# PT80.net
KiCad netlist of a schematic drawn in EAGLE
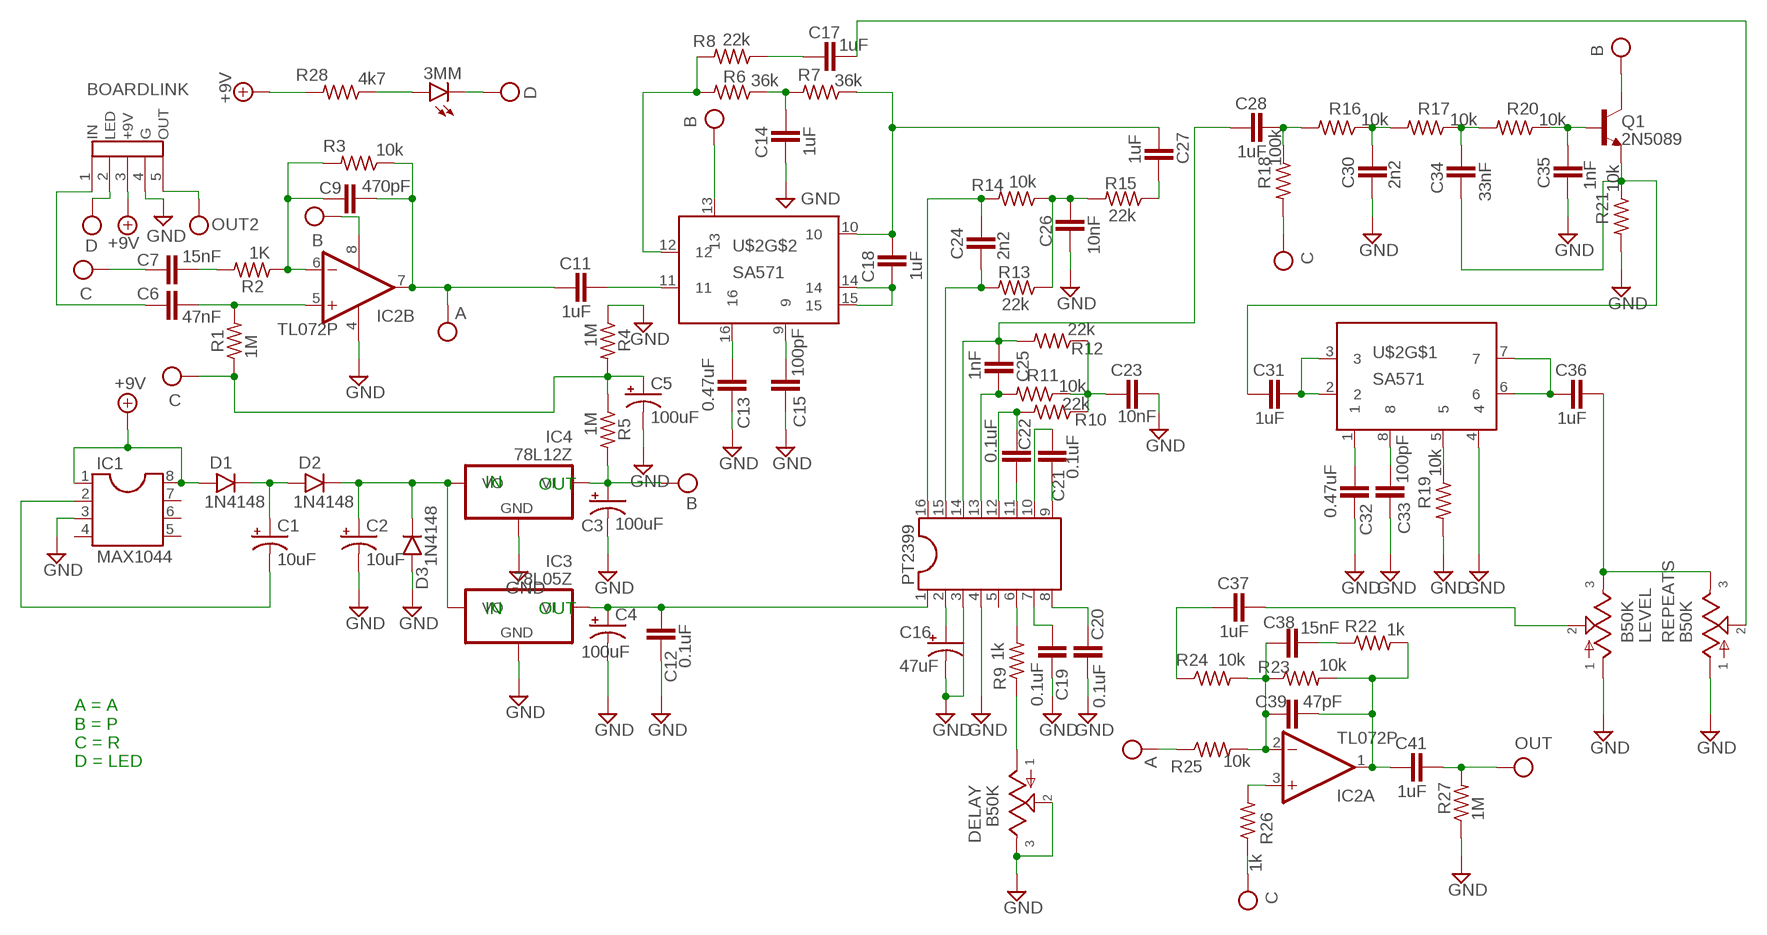
[diagram p0: schematic, sheet 1]

(export (version "E")
  (design (tool "Eeschema 10.0.6"))
  (components
    (comp (ref "3MM")
      (value "LED3MM")
      (footprint "eagle-import:LED3MM")
      (libsource (lib "eagle-import") (part "LED3MM"))
    )
    (comp (ref "C1")
      (value "10uF")
      (footprint "eagle-import:050_020_1")
      (libsource (lib "eagle-import") (part "0501"))
    )
    (comp (ref "C2")
      (value "10uF")
      (footprint "eagle-import:050_020_1")
      (libsource (lib "eagle-import") (part "0501"))
    )
    (comp (ref "C3")
      (value "100uF")
      (footprint "eagle-import:080_035_1")
      (libsource (lib "eagle-import") (part "0801"))
    )
    (comp (ref "C4")
      (value "100uF")
      (footprint "eagle-import:080_035_1")
      (libsource (lib "eagle-import") (part "0801"))
    )
    (comp (ref "C5")
      (value "100uF")
      (footprint "eagle-import:080_035_1")
      (libsource (lib "eagle-import") (part "0801"))
    )
    (comp (ref "C6")
      (value "47nF")
      (footprint "eagle-import:072X035")
      (libsource (lib "eagle-import") (part "072X0352"))
    )
    (comp (ref "C7")
      (value "15nF")
      (footprint "eagle-import:072X025")
      (libsource (lib "eagle-import") (part "072X0252"))
    )
    (comp (ref "C9")
      (value "470pF")
      (footprint "eagle-import:050X030_025")
      (libsource (lib "eagle-import") (part "050X030_0251"))
    )
    (comp (ref "C11")
      (value "1uF")
      (footprint "eagle-import:072X045")
      (libsource (lib "eagle-import") (part "072X0452"))
    )
    (comp (ref "C12")
      (value "0.1uF")
      (footprint "eagle-import:072X035")
      (libsource (lib "eagle-import") (part "072X0352"))
    )
    (comp (ref "C13")
      (value "0.47uF")
      (footprint "eagle-import:072X035")
      (libsource (lib "eagle-import") (part "072X0352"))
    )
    (comp (ref "C14")
      (value "1uF")
      (footprint "eagle-import:072X045")
      (libsource (lib "eagle-import") (part "072X0452"))
    )
    (comp (ref "C15")
      (value "100pF")
      (footprint "eagle-import:050X030_025")
      (libsource (lib "eagle-import") (part "050X030_0251"))
    )
    (comp (ref "C16")
      (value "47uF")
      (footprint "eagle-import:063_025")
      (libsource (lib "eagle-import") (part "0631"))
    )
    (comp (ref "C17")
      (value "1uF")
      (footprint "eagle-import:072X045")
      (libsource (lib "eagle-import") (part "072X0452"))
    )
    (comp (ref "C18")
      (value "1uF")
      (footprint "eagle-import:072X045")
      (libsource (lib "eagle-import") (part "072X0452"))
    )
    (comp (ref "C19")
      (value "0.1uF")
      (footprint "eagle-import:072X035")
      (libsource (lib "eagle-import") (part "072X0352"))
    )
    (comp (ref "C20")
      (value "0.1uF")
      (footprint "eagle-import:072X035")
      (libsource (lib "eagle-import") (part "072X0352"))
    )
    (comp (ref "C21")
      (value "0.1uF")
      (footprint "eagle-import:072X035")
      (libsource (lib "eagle-import") (part "072X0352"))
    )
    (comp (ref "C22")
      (value "0.1uF")
      (footprint "eagle-import:072X035")
      (libsource (lib "eagle-import") (part "072X0352"))
    )
    (comp (ref "C23")
      (value "10nF")
      (footprint "eagle-import:072X025")
      (libsource (lib "eagle-import") (part "072X0252"))
    )
    (comp (ref "C24")
      (value "2n2")
      (footprint "eagle-import:072X025")
      (libsource (lib "eagle-import") (part "072X0252"))
    )
    (comp (ref "C25")
      (value "1nF")
      (footprint "eagle-import:072X025")
      (libsource (lib "eagle-import") (part "072X0252"))
    )
    (comp (ref "C26")
      (value "10nF")
      (footprint "eagle-import:072X025")
      (libsource (lib "eagle-import") (part "072X0252"))
    )
    (comp (ref "C27")
      (value "1uF")
      (footprint "eagle-import:072X045")
      (libsource (lib "eagle-import") (part "072X0452"))
    )
    (comp (ref "C28")
      (value "1uF")
      (footprint "eagle-import:072X045")
      (libsource (lib "eagle-import") (part "072X0452"))
    )
    (comp (ref "C30")
      (value "2n2")
      (footprint "eagle-import:072X025")
      (libsource (lib "eagle-import") (part "072X0252"))
    )
    (comp (ref "C31")
      (value "1uF")
      (footprint "eagle-import:072X045")
      (libsource (lib "eagle-import") (part "072X0452"))
    )
    (comp (ref "C32")
      (value "0.47uF")
      (footprint "eagle-import:072X035")
      (libsource (lib "eagle-import") (part "072X0352"))
    )
    (comp (ref "C33")
      (value "100pF")
      (footprint "eagle-import:050X030_025")
      (libsource (lib "eagle-import") (part "050X030_0251"))
    )
    (comp (ref "C34")
      (value "33nF")
      (footprint "eagle-import:072X025")
      (libsource (lib "eagle-import") (part "072X0252"))
    )
    (comp (ref "C35")
      (value "1nF")
      (footprint "eagle-import:072X025")
      (libsource (lib "eagle-import") (part "072X0252"))
    )
    (comp (ref "C36")
      (value "1uF")
      (footprint "eagle-import:072X045")
      (libsource (lib "eagle-import") (part "072X0452"))
    )
    (comp (ref "C37")
      (value "1uF")
      (footprint "eagle-import:072X045")
      (libsource (lib "eagle-import") (part "072X0452"))
    )
    (comp (ref "C38")
      (value "15nF")
      (footprint "eagle-import:072X025")
      (libsource (lib "eagle-import") (part "072X0252"))
    )
    (comp (ref "C39")
      (value "47pF")
      (footprint "eagle-import:050X030_025")
      (libsource (lib "eagle-import") (part "050X030_0251"))
    )
    (comp (ref "C41")
      (value "1uF")
      (footprint "eagle-import:072X045")
      (libsource (lib "eagle-import") (part "072X0452"))
    )
    (comp (ref "D1")
      (value "1N4148")
      (footprint "eagle-import:DO35-3")
      (libsource (lib "eagle-import") (part "1N4148-3"))
    )
    (comp (ref "D2")
      (value "1N4148")
      (footprint "eagle-import:DO35-3")
      (libsource (lib "eagle-import") (part "1N4148-3"))
    )
    (comp (ref "D3")
      (value "1N4148")
      (footprint "eagle-import:DO35-3")
      (libsource (lib "eagle-import") (part "1N4148-3"))
    )
    (comp (ref "DELAY")
      (value "B50K")
      (footprint "eagle-import:16MM")
      (libsource (lib "eagle-import") (part "POT16MM"))
    )
    (comp (ref "IC1")
      (value "MAX1044")
      (footprint "eagle-import:DIL08")
      (libsource (lib "eagle-import") (part "MAX1044"))
    )
    (comp (ref "IC2")
      (value "TL072P")
      (footprint "eagle-import:DIL08")
      (libsource (lib "eagle-import") (part "TL072P"))
    )
    (comp (ref "IC3")
      (value "78L05Z")
      (footprint "eagle-import:TO92")
      (libsource (lib "eagle-import") (part "78ZL05"))
    )
    (comp (ref "IC4")
      (value "78L12Z")
      (footprint "eagle-import:TO92")
      (libsource (lib "eagle-import") (part "78ZL12"))
    )
    (comp (ref "LEVEL")
      (value "B50K")
      (footprint "eagle-import:16MM")
      (libsource (lib "eagle-import") (part "POT16MM"))
    )
    (comp (ref "PT2399")
      (value "DIL16")
      (footprint "eagle-import:DIL16")
      (libsource (lib "eagle-import") (part "DIL16"))
    )
    (comp (ref "Q1")
      (value "2N5089")
      (footprint "eagle-import:TO92-")
      (libsource (lib "eagle-import") (part "2N5089"))
    )
    (comp (ref "R1")
      (value "1M")
      (footprint "eagle-import:R0207_3")
      (libsource (lib "eagle-import") (part "6MM.3"))
    )
    (comp (ref "R2")
      (value "1K")
      (footprint "eagle-import:R0207_3")
      (libsource (lib "eagle-import") (part "6MM.3"))
    )
    (comp (ref "R3")
      (value "10k")
      (footprint "eagle-import:R0207_3")
      (libsource (lib "eagle-import") (part "6MM.3"))
    )
    (comp (ref "R4")
      (value "1M")
      (footprint "eagle-import:R0207_3")
      (libsource (lib "eagle-import") (part "6MM.3"))
    )
    (comp (ref "R5")
      (value "1M")
      (footprint "eagle-import:R0207_3")
      (libsource (lib "eagle-import") (part "6MM.3"))
    )
    (comp (ref "R6")
      (value "36k")
      (footprint "eagle-import:R0207_3")
      (libsource (lib "eagle-import") (part "6MM.3"))
    )
    (comp (ref "R7")
      (value "36k")
      (footprint "eagle-import:R0207_3")
      (libsource (lib "eagle-import") (part "6MM.3"))
    )
    (comp (ref "R8")
      (value "22k")
      (footprint "eagle-import:R0207_3")
      (libsource (lib "eagle-import") (part "6MM.3"))
    )
    (comp (ref "R9")
      (value "1k")
      (footprint "eagle-import:R0207_3")
      (libsource (lib "eagle-import") (part "6MM.3"))
    )
    (comp (ref "R10")
      (value "22k")
      (footprint "eagle-import:R0207_3")
      (libsource (lib "eagle-import") (part "6MM.3"))
    )
    (comp (ref "R11")
      (value "10k")
      (footprint "eagle-import:R0207_3")
      (libsource (lib "eagle-import") (part "6MM.3"))
    )
    (comp (ref "R12")
      (value "22k")
      (footprint "eagle-import:R0207_3")
      (libsource (lib "eagle-import") (part "6MM.3"))
    )
    (comp (ref "R13")
      (value "22k")
      (footprint "eagle-import:R0207_3")
      (libsource (lib "eagle-import") (part "6MM.3"))
    )
    (comp (ref "R14")
      (value "10k")
      (footprint "eagle-import:R0207_3")
      (libsource (lib "eagle-import") (part "6MM.3"))
    )
    (comp (ref "R15")
      (value "22k")
      (footprint "eagle-import:R0207_3")
      (libsource (lib "eagle-import") (part "6MM.3"))
    )
    (comp (ref "R16")
      (value "10k")
      (footprint "eagle-import:R0207_3")
      (libsource (lib "eagle-import") (part "6MM.3"))
    )
    (comp (ref "R17")
      (value "10k")
      (footprint "eagle-import:R0207_3")
      (libsource (lib "eagle-import") (part "6MM.3"))
    )
    (comp (ref "R18")
      (value "100k")
      (footprint "eagle-import:R0207_3")
      (libsource (lib "eagle-import") (part "6MM.3"))
    )
    (comp (ref "R19")
      (value "10k")
      (footprint "eagle-import:R0207_3")
      (libsource (lib "eagle-import") (part "6MM.3"))
    )
    (comp (ref "R20")
      (value "10k")
      (footprint "eagle-import:R0207_3")
      (libsource (lib "eagle-import") (part "6MM.3"))
    )
    (comp (ref "R21")
      (value "10k")
      (footprint "eagle-import:R0207_3")
      (libsource (lib "eagle-import") (part "6MM.3"))
    )
    (comp (ref "R22")
      (value "1k")
      (footprint "eagle-import:R0207_3")
      (libsource (lib "eagle-import") (part "6MM.3"))
    )
    (comp (ref "R23")
      (value "10k")
      (footprint "eagle-import:R0207_3")
      (libsource (lib "eagle-import") (part "6MM.3"))
    )
    (comp (ref "R24")
      (value "10k")
      (footprint "eagle-import:R0207_3")
      (libsource (lib "eagle-import") (part "6MM.3"))
    )
    (comp (ref "R25")
      (value "10k")
      (footprint "eagle-import:R0207_3")
      (libsource (lib "eagle-import") (part "6MM.3"))
    )
    (comp (ref "R26")
      (value "1k")
      (footprint "eagle-import:R0207_3")
      (libsource (lib "eagle-import") (part "6MM.3"))
    )
    (comp (ref "R27")
      (value "1M")
      (footprint "eagle-import:R0207_3")
      (libsource (lib "eagle-import") (part "6MM.3"))
    )
    (comp (ref "R28")
      (value "4k7")
      (footprint "eagle-import:R0207_3")
      (libsource (lib "eagle-import") (part "6MM.3"))
    )
    (comp (ref "REPEATS")
      (value "B50K")
      (footprint "eagle-import:16MM")
      (libsource (lib "eagle-import") (part "POT16MM"))
    )
    (comp (ref "U$1")
      (value "BOARDLINK")
      (footprint "eagle-import:BOARDLINK")
      (libsource (lib "eagle-import") (part "BOARDLINK"))
    )
    (comp (ref "U$2")
      (value "SA571")
      (footprint "eagle-import:DIL16")
      (libsource (lib "eagle-import") (part "SA571"))
    )
  )
  (nets
    (net (code "1") (name "+9V") (class "Default")
      (node (ref "D1") (pin "A") (pinfunction "A_A") (pintype "passive"))
      (node (ref "IC1") (pin "1") (pinfunction "1_1") (pintype "passive"))
      (node (ref "IC1") (pin "8") (pinfunction "8_8") (pintype "passive"))
      (node (ref "R28") (pin "2") (pinfunction "2_2") (pintype "passive"))
      (node (ref "U$1") (pin "3") (pinfunction "+9V_3") (pintype "bidirectional"))
    )
    (net (code "2") (name "A") (class "Default")
      (node (ref "C11") (pin "1") (pinfunction "1_1") (pintype "passive"))
      (node (ref "C9") (pin "2") (pinfunction "2_2") (pintype "passive"))
      (node (ref "IC2") (pin "7") (pinfunction "OUT_7") (pintype "output"))
      (node (ref "R25") (pin "1") (pinfunction "1_1") (pintype "passive"))
      (node (ref "R3") (pin "1") (pinfunction "1_1") (pintype "passive"))
    )
    (net (code "3") (name "B") (class "Default")
      (node (ref "C3") (pin "+") (pinfunction "+_+") (pintype "passive"))
      (node (ref "IC2") (pin "8") (pinfunction "V+_8") (pintype "power_in"))
      (node (ref "IC4") (pin "1") (pinfunction "VI_1") (pintype "input"))
      (node (ref "Q1") (pin "1") (pinfunction "C_1") (pintype "passive"))
      (node (ref "R5") (pin "2") (pinfunction "2_2") (pintype "passive"))
      (node (ref "U$2") (pin "13") (pinfunction "13_13") (pintype "bidirectional"))
    )
    (net (code "4") (name "C") (class "Default")
      (node (ref "C5") (pin "+") (pinfunction "+_+") (pintype "passive"))
      (node (ref "C7") (pin "1") (pinfunction "1_1") (pintype "passive"))
      (node (ref "R1") (pin "1") (pinfunction "1_1") (pintype "passive"))
      (node (ref "R18") (pin "2") (pinfunction "2_2") (pintype "passive"))
      (node (ref "R26") (pin "1") (pinfunction "1_1") (pintype "passive"))
      (node (ref "R4") (pin "2") (pinfunction "2_2") (pintype "passive"))
      (node (ref "R5") (pin "1") (pinfunction "1_1") (pintype "passive"))
    )
    (net (code "5") (name "D") (class "Default")
      (node (ref "3MM") (pin "K") (pinfunction "C_K") (pintype "passive"))
      (node (ref "U$1") (pin "2") (pinfunction "LED_2") (pintype "bidirectional"))
    )
    (net (code "6") (name "GND") (class "Default")
      (node (ref "C12") (pin "1") (pinfunction "1_1") (pintype "passive"))
      (node (ref "C13") (pin "2") (pinfunction "2_2") (pintype "passive"))
      (node (ref "C14") (pin "1") (pinfunction "1_1") (pintype "passive"))
      (node (ref "C15") (pin "1") (pinfunction "1_1") (pintype "passive"))
      (node (ref "C16") (pin "-") (pinfunction "-_-") (pintype "passive"))
      (node (ref "C19") (pin "2") (pinfunction "2_2") (pintype "passive"))
      (node (ref "C2") (pin "-") (pinfunction "-_-") (pintype "passive"))
      (node (ref "C20") (pin "2") (pinfunction "2_2") (pintype "passive"))
      (node (ref "C23") (pin "2") (pinfunction "2_2") (pintype "passive"))
      (node (ref "C26") (pin "1") (pinfunction "1_1") (pintype "passive"))
      (node (ref "C3") (pin "-") (pinfunction "-_-") (pintype "passive"))
      (node (ref "C30") (pin "1") (pinfunction "1_1") (pintype "passive"))
      (node (ref "C32") (pin "2") (pinfunction "2_2") (pintype "passive"))
      (node (ref "C33") (pin "1") (pinfunction "1_1") (pintype "passive"))
      (node (ref "C35") (pin "1") (pinfunction "1_1") (pintype "passive"))
      (node (ref "C4") (pin "-") (pinfunction "-_-") (pintype "passive"))
      (node (ref "C5") (pin "-") (pinfunction "-_-") (pintype "passive"))
      (node (ref "D3") (pin "A") (pinfunction "A_A") (pintype "passive"))
      (node (ref "DELAY") (pin "2") (pinfunction "2_2") (pintype "passive"))
      (node (ref "DELAY") (pin "3") (pinfunction "3_3") (pintype "passive"))
      (node (ref "IC1") (pin "3") (pinfunction "3_3") (pintype "passive"))
      (node (ref "IC2") (pin "4") (pinfunction "V-_4") (pintype "power_in"))
      (node (ref "IC3") (pin "2") (pinfunction "GND_2") (pintype "passive"))
      (node (ref "IC4") (pin "2") (pinfunction "GND_2") (pintype "passive"))
      (node (ref "LEVEL") (pin "1") (pinfunction "1_1") (pintype "passive"))
      (node (ref "PT2399") (pin "3") (pinfunction "3_3") (pintype "passive"))
      (node (ref "PT2399") (pin "4") (pinfunction "4_4") (pintype "passive"))
      (node (ref "R19") (pin "2") (pinfunction "2_2") (pintype "passive"))
      (node (ref "R21") (pin "2") (pinfunction "2_2") (pintype "passive"))
      (node (ref "R27") (pin "1") (pinfunction "1_1") (pintype "passive"))
      (node (ref "R4") (pin "1") (pinfunction "1_1") (pintype "passive"))
      (node (ref "REPEATS") (pin "1") (pinfunction "1_1") (pintype "passive"))
      (node (ref "U$1") (pin "4") (pinfunction "G_4") (pintype "bidirectional"))
      (node (ref "U$2") (pin "4") (pinfunction "4_4") (pintype "bidirectional"))
    )
    (net (code "7") (name "Net-(3MM-PadA)") (class "Default")
      (node (ref "3MM") (pin "A") (pinfunction "A_A") (pintype "passive"))
      (node (ref "R28") (pin "1") (pinfunction "1_1") (pintype "passive"))
    )
    (net (code "8") (name "Net-(C1-Pad+)") (class "Default")
      (node (ref "C1") (pin "+") (pinfunction "+_+") (pintype "passive"))
      (node (ref "D1") (pin "C") (pinfunction "C_C") (pintype "passive"))
      (node (ref "D2") (pin "A") (pinfunction "A_A") (pintype "passive"))
    )
    (net (code "9") (name "Net-(C1-Pad-)") (class "Default")
      (node (ref "C1") (pin "-") (pinfunction "-_-") (pintype "passive"))
      (node (ref "IC1") (pin "2") (pinfunction "2_2") (pintype "passive"))
    )
    (net (code "10") (name "Net-(C7-Pad2)") (class "Default")
      (node (ref "C7") (pin "2") (pinfunction "2_2") (pintype "passive"))
      (node (ref "R2") (pin "2") (pinfunction "2_2") (pintype "passive"))
    )
    (net (code "11") (name "Net-(C11-Pad2)") (class "Default")
      (node (ref "C11") (pin "2") (pinfunction "2_2") (pintype "passive"))
      (node (ref "U$2") (pin "11") (pinfunction "11_11") (pintype "bidirectional"))
    )
    (net (code "12") (name "Net-(C13-Pad1)") (class "Default")
      (node (ref "C13") (pin "1") (pinfunction "1_1") (pintype "passive"))
      (node (ref "U$2") (pin "16") (pinfunction "16_16") (pintype "bidirectional"))
    )
    (net (code "13") (name "Net-(C14-Pad2)") (class "Default")
      (node (ref "C14") (pin "2") (pinfunction "2_2") (pintype "passive"))
      (node (ref "R6") (pin "1") (pinfunction "1_1") (pintype "passive"))
      (node (ref "R7") (pin "2") (pinfunction "2_2") (pintype "passive"))
    )
    (net (code "14") (name "Net-(C15-Pad2)") (class "Default")
      (node (ref "C15") (pin "2") (pinfunction "2_2") (pintype "passive"))
      (node (ref "U$2") (pin "9") (pinfunction "9_9") (pintype "bidirectional"))
    )
    (net (code "15") (name "Net-(C16-Pad+)") (class "Default")
      (node (ref "C16") (pin "+") (pinfunction "+_+") (pintype "passive"))
      (node (ref "PT2399") (pin "2") (pinfunction "2_2") (pintype "passive"))
    )
    (net (code "16") (name "Net-(C17-Pad1)") (class "Default")
      (node (ref "C17") (pin "1") (pinfunction "1_1") (pintype "passive"))
      (node (ref "R8") (pin "1") (pinfunction "1_1") (pintype "passive"))
    )
    (net (code "17") (name "Net-(C17-Pad2)") (class "Default")
      (node (ref "C17") (pin "2") (pinfunction "2_2") (pintype "passive"))
      (node (ref "REPEATS") (pin "2") (pinfunction "2_2") (pintype "passive"))
    )
    (net (code "18") (name "Net-(C18-Pad1)") (class "Default")
      (node (ref "C18") (pin "1") (pinfunction "1_1") (pintype "passive"))
      (node (ref "U$2") (pin "14") (pinfunction "14_14") (pintype "bidirectional"))
      (node (ref "U$2") (pin "15") (pinfunction "15_15") (pintype "bidirectional"))
    )
    (net (code "19") (name "Net-(C18-Pad2)") (class "Default")
      (node (ref "C18") (pin "2") (pinfunction "2_2") (pintype "passive"))
      (node (ref "C27") (pin "1") (pinfunction "1_1") (pintype "passive"))
      (node (ref "R7") (pin "1") (pinfunction "1_1") (pintype "passive"))
      (node (ref "U$2") (pin "10") (pinfunction "10_10") (pintype "bidirectional"))
    )
    (net (code "20") (name "Net-(C19-Pad1)") (class "Default")
      (node (ref "C19") (pin "1") (pinfunction "1_1") (pintype "passive"))
      (node (ref "PT2399") (pin "7") (pinfunction "7_7") (pintype "passive"))
    )
    (net (code "21") (name "Net-(C20-Pad1)") (class "Default")
      (node (ref "C20") (pin "1") (pinfunction "1_1") (pintype "passive"))
      (node (ref "PT2399") (pin "8") (pinfunction "8_8") (pintype "passive"))
    )
    (net (code "22") (name "Net-(C21-Pad1)") (class "Default")
      (node (ref "C21") (pin "1") (pinfunction "1_1") (pintype "passive"))
      (node (ref "PT2399") (pin "10") (pinfunction "10_10") (pintype "passive"))
    )
    (net (code "23") (name "Net-(C21-Pad2)") (class "Default")
      (node (ref "C21") (pin "2") (pinfunction "2_2") (pintype "passive"))
      (node (ref "PT2399") (pin "9") (pinfunction "9_9") (pintype "passive"))
    )
    (net (code "24") (name "Net-(C22-Pad1)") (class "Default")
      (node (ref "C22") (pin "1") (pinfunction "1_1") (pintype "passive"))
      (node (ref "PT2399") (pin "12") (pinfunction "12_12") (pintype "passive"))
      (node (ref "R10") (pin "2") (pinfunction "2_2") (pintype "passive"))
    )
    (net (code "25") (name "Net-(C22-Pad2)") (class "Default")
      (node (ref "C22") (pin "2") (pinfunction "2_2") (pintype "passive"))
      (node (ref "PT2399") (pin "11") (pinfunction "11_11") (pintype "passive"))
    )
    (net (code "26") (name "Net-(C23-Pad1)") (class "Default")
      (node (ref "C23") (pin "1") (pinfunction "1_1") (pintype "passive"))
      (node (ref "R10") (pin "1") (pinfunction "1_1") (pintype "passive"))
      (node (ref "R11") (pin "1") (pinfunction "1_1") (pintype "passive"))
      (node (ref "R12") (pin "1") (pinfunction "1_1") (pintype "passive"))
    )
    (net (code "27") (name "Net-(C24-Pad1)") (class "Default")
      (node (ref "C24") (pin "1") (pinfunction "1_1") (pintype "passive"))
      (node (ref "PT2399") (pin "15") (pinfunction "15_15") (pintype "passive"))
      (node (ref "R13") (pin "2") (pinfunction "2_2") (pintype "passive"))
    )
    (net (code "28") (name "Net-(C24-Pad2)") (class "Default")
      (node (ref "C24") (pin "2") (pinfunction "2_2") (pintype "passive"))
      (node (ref "PT2399") (pin "16") (pinfunction "16_16") (pintype "passive"))
      (node (ref "R14") (pin "2") (pinfunction "2_2") (pintype "passive"))
    )
    (net (code "29") (name "Net-(C25-Pad1)") (class "Default")
      (node (ref "C25") (pin "1") (pinfunction "1_1") (pintype "passive"))
      (node (ref "PT2399") (pin "13") (pinfunction "13_13") (pintype "passive"))
      (node (ref "R11") (pin "2") (pinfunction "2_2") (pintype "passive"))
    )
    (net (code "30") (name "Net-(C25-Pad2)") (class "Default")
      (node (ref "C25") (pin "2") (pinfunction "2_2") (pintype "passive"))
      (node (ref "C28") (pin "1") (pinfunction "1_1") (pintype "passive"))
      (node (ref "PT2399") (pin "14") (pinfunction "14_14") (pintype "passive"))
      (node (ref "R12") (pin "2") (pinfunction "2_2") (pintype "passive"))
    )
    (net (code "31") (name "Net-(C26-Pad2)") (class "Default")
      (node (ref "C26") (pin "2") (pinfunction "2_2") (pintype "passive"))
      (node (ref "R13") (pin "1") (pinfunction "1_1") (pintype "passive"))
      (node (ref "R14") (pin "1") (pinfunction "1_1") (pintype "passive"))
      (node (ref "R15") (pin "2") (pinfunction "2_2") (pintype "passive"))
    )
    (net (code "32") (name "Net-(C27-Pad2)") (class "Default")
      (node (ref "C27") (pin "2") (pinfunction "2_2") (pintype "passive"))
      (node (ref "R15") (pin "1") (pinfunction "1_1") (pintype "passive"))
    )
    (net (code "33") (name "Net-(C28-Pad2)") (class "Default")
      (node (ref "C28") (pin "2") (pinfunction "2_2") (pintype "passive"))
      (node (ref "R16") (pin "2") (pinfunction "2_2") (pintype "passive"))
      (node (ref "R18") (pin "1") (pinfunction "1_1") (pintype "passive"))
    )
    (net (code "34") (name "Net-(C30-Pad2)") (class "Default")
      (node (ref "C30") (pin "2") (pinfunction "2_2") (pintype "passive"))
      (node (ref "R16") (pin "1") (pinfunction "1_1") (pintype "passive"))
      (node (ref "R17") (pin "2") (pinfunction "2_2") (pintype "passive"))
    )
    (net (code "35") (name "Net-(C31-Pad2)") (class "Default")
      (node (ref "C31") (pin "2") (pinfunction "2_2") (pintype "passive"))
      (node (ref "U$2") (pin "2") (pinfunction "2_2") (pintype "bidirectional"))
      (node (ref "U$2") (pin "3") (pinfunction "3_3") (pintype "bidirectional"))
    )
    (net (code "36") (name "Net-(C32-Pad1)") (class "Default")
      (node (ref "C32") (pin "1") (pinfunction "1_1") (pintype "passive"))
      (node (ref "U$2") (pin "1") (pinfunction "1_1") (pintype "bidirectional"))
    )
    (net (code "37") (name "Net-(C33-Pad2)") (class "Default")
      (node (ref "C33") (pin "2") (pinfunction "2_2") (pintype "passive"))
      (node (ref "U$2") (pin "8") (pinfunction "8_8") (pintype "bidirectional"))
    )
    (net (code "38") (name "Net-(C34-Pad2)") (class "Default")
      (node (ref "C34") (pin "2") (pinfunction "2_2") (pintype "passive"))
      (node (ref "R17") (pin "1") (pinfunction "1_1") (pintype "passive"))
      (node (ref "R20") (pin "2") (pinfunction "2_2") (pintype "passive"))
    )
    (net (code "39") (name "Net-(C36-Pad1)") (class "Default")
      (node (ref "C36") (pin "1") (pinfunction "1_1") (pintype "passive"))
      (node (ref "U$2") (pin "6") (pinfunction "6_6") (pintype "bidirectional"))
      (node (ref "U$2") (pin "7") (pinfunction "7_7") (pintype "bidirectional"))
    )
    (net (code "40") (name "Net-(C36-Pad2)") (class "Default")
      (node (ref "C36") (pin "2") (pinfunction "2_2") (pintype "passive"))
      (node (ref "LEVEL") (pin "3") (pinfunction "3_3") (pintype "passive"))
      (node (ref "REPEATS") (pin "3") (pinfunction "3_3") (pintype "passive"))
    )
    (net (code "41") (name "Net-(C37-Pad1)") (class "Default")
      (node (ref "C37") (pin "1") (pinfunction "1_1") (pintype "passive"))
      (node (ref "R24") (pin "1") (pinfunction "1_1") (pintype "passive"))
    )
    (net (code "42") (name "Net-(C37-Pad2)") (class "Default")
      (node (ref "C37") (pin "2") (pinfunction "2_2") (pintype "passive"))
      (node (ref "LEVEL") (pin "2") (pinfunction "2_2") (pintype "passive"))
    )
    (net (code "43") (name "Net-(C38-Pad1)") (class "Default")
      (node (ref "C38") (pin "1") (pinfunction "1_1") (pintype "passive"))
      (node (ref "R22") (pin "1") (pinfunction "1_1") (pintype "passive"))
    )
    (net (code "44") (name "Net-(DELAY-Pad1)") (class "Default")
      (node (ref "DELAY") (pin "1") (pinfunction "1_1") (pintype "passive"))
      (node (ref "R9") (pin "1") (pinfunction "1_1") (pintype "passive"))
    )
    (net (code "45") (name "Net-(IC2A-+IN)") (class "Default")
      (node (ref "IC2") (pin "3") (pinfunction "+IN_3") (pintype "input"))
      (node (ref "R26") (pin "2") (pinfunction "2_2") (pintype "passive"))
    )
    (net (code "46") (name "Net-(IC2A--IN)") (class "Default")
      (node (ref "C38") (pin "2") (pinfunction "2_2") (pintype "passive"))
      (node (ref "C39") (pin "2") (pinfunction "2_2") (pintype "passive"))
      (node (ref "IC2") (pin "2") (pinfunction "-IN_2") (pintype "input"))
      (node (ref "R23") (pin "1") (pinfunction "1_1") (pintype "passive"))
      (node (ref "R24") (pin "2") (pinfunction "2_2") (pintype "passive"))
      (node (ref "R25") (pin "2") (pinfunction "2_2") (pintype "passive"))
    )
    (net (code "47") (name "Net-(IC2A-OUT)") (class "Default")
      (node (ref "C39") (pin "1") (pinfunction "1_1") (pintype "passive"))
      (node (ref "C41") (pin "1") (pinfunction "1_1") (pintype "passive"))
      (node (ref "IC2") (pin "1") (pinfunction "OUT_1") (pintype "output"))
      (node (ref "R22") (pin "2") (pinfunction "2_2") (pintype "passive"))
      (node (ref "R23") (pin "2") (pinfunction "2_2") (pintype "passive"))
    )
    (net (code "48") (name "Net-(IC2B-+IN)") (class "Default")
      (node (ref "C6") (pin "2") (pinfunction "2_2") (pintype "passive"))
      (node (ref "IC2") (pin "5") (pinfunction "+IN_5") (pintype "input"))
      (node (ref "R1") (pin "2") (pinfunction "2_2") (pintype "passive"))
    )
    (net (code "49") (name "Net-(IC2B--IN)") (class "Default")
      (node (ref "C9") (pin "1") (pinfunction "1_1") (pintype "passive"))
      (node (ref "IC2") (pin "6") (pinfunction "-IN_6") (pintype "input"))
      (node (ref "R2") (pin "1") (pinfunction "1_1") (pintype "passive"))
      (node (ref "R3") (pin "2") (pinfunction "2_2") (pintype "passive"))
    )
    (net (code "50") (name "Net-(IC3-VI)") (class "Default")
      (node (ref "C12") (pin "2") (pinfunction "2_2") (pintype "passive"))
      (node (ref "C4") (pin "+") (pinfunction "+_+") (pintype "passive"))
      (node (ref "IC3") (pin "1") (pinfunction "VI_1") (pintype "input"))
      (node (ref "PT2399") (pin "1") (pinfunction "1_1") (pintype "passive"))
    )
    (net (code "51") (name "Net-(IC3-VO)") (class "Default")
      (node (ref "C2") (pin "+") (pinfunction "+_+") (pintype "passive"))
      (node (ref "D2") (pin "C") (pinfunction "C_C") (pintype "passive"))
      (node (ref "D3") (pin "C") (pinfunction "C_C") (pintype "passive"))
      (node (ref "IC3") (pin "3") (pinfunction "VO_3") (pintype "passive"))
      (node (ref "IC4") (pin "3") (pinfunction "VO_3") (pintype "passive"))
    )
    (net (code "52") (name "Net-(PT2399-Pad6)") (class "Default")
      (node (ref "PT2399") (pin "6") (pinfunction "6_6") (pintype "passive"))
      (node (ref "R9") (pin "2") (pinfunction "2_2") (pintype "passive"))
    )
    (net (code "53") (name "Net-(Q1-B)") (class "Default")
      (node (ref "C35") (pin "2") (pinfunction "2_2") (pintype "passive"))
      (node (ref "Q1") (pin "2") (pinfunction "B_2") (pintype "passive"))
      (node (ref "R20") (pin "1") (pinfunction "1_1") (pintype "passive"))
    )
    (net (code "54") (name "Net-(Q1-E)") (class "Default")
      (node (ref "C31") (pin "1") (pinfunction "1_1") (pintype "passive"))
      (node (ref "C34") (pin "1") (pinfunction "1_1") (pintype "passive"))
      (node (ref "Q1") (pin "3") (pinfunction "E_3") (pintype "passive"))
      (node (ref "R21") (pin "1") (pinfunction "1_1") (pintype "passive"))
    )
    (net (code "55") (name "Net-(R6-Pad2)") (class "Default")
      (node (ref "R6") (pin "2") (pinfunction "2_2") (pintype "passive"))
      (node (ref "R8") (pin "2") (pinfunction "2_2") (pintype "passive"))
      (node (ref "U$2") (pin "12") (pinfunction "12_12") (pintype "bidirectional"))
    )
    (net (code "56") (name "Net-(R19-Pad1)") (class "Default")
      (node (ref "R19") (pin "1") (pinfunction "1_1") (pintype "passive"))
      (node (ref "U$2") (pin "5") (pinfunction "5_5") (pintype "bidirectional"))
    )
    (net (code "57") (name "Net-(U$1-IN)") (class "Default")
      (node (ref "C6") (pin "1") (pinfunction "1_1") (pintype "passive"))
      (node (ref "U$1") (pin "1") (pinfunction "IN_1") (pintype "bidirectional"))
    )
    (net (code "58") (name "OUT") (class "Default")
      (node (ref "C41") (pin "2") (pinfunction "2_2") (pintype "passive"))
      (node (ref "R27") (pin "2") (pinfunction "2_2") (pintype "passive"))
      (node (ref "U$1") (pin "5") (pinfunction "OUT_5") (pintype "bidirectional"))
    )
    (net (code "59") (name "unconnected-(IC1-Pad4)") (class "Default")
      (node (ref "IC1") (pin "4") (pinfunction "4_4") (pintype "passive"))
    )
    (net (code "60") (name "unconnected-(IC1-Pad5)") (class "Default")
      (node (ref "IC1") (pin "5") (pinfunction "5_5") (pintype "passive"))
    )
    (net (code "61") (name "unconnected-(IC1-Pad6)") (class "Default")
      (node (ref "IC1") (pin "6") (pinfunction "6_6") (pintype "passive"))
    )
    (net (code "62") (name "unconnected-(IC1-Pad7)") (class "Default")
      (node (ref "IC1") (pin "7") (pinfunction "7_7") (pintype "passive"))
    )
    (net (code "63") (name "unconnected-(PT2399-Pad5)") (class "Default")
      (node (ref "PT2399") (pin "5") (pinfunction "5_5") (pintype "passive"))
    )
  )
)
